# jack2jst.net
KiCad netlist of a schematic drawn in EAGLE
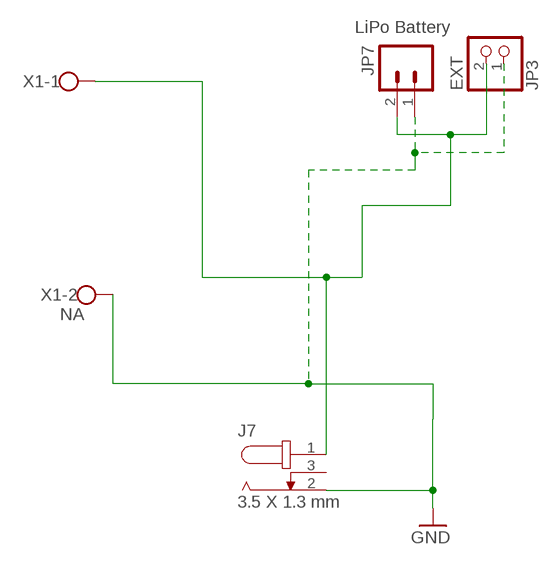
[diagram p0: schematic, sheet 1]

(export (version "E")
  (design (tool "Eeschema 10.0.6"))
  (components
    (comp (ref "J7")
      (value "3.5 X 1.3 mm")
      (footprint "eagle-import:3.5X1.3MM_DC_JACK")
      (libsource (lib "eagle-import") (part "DC_JACK_3.5X1.3MM"))
    )
    (comp (ref "JP3")
      (value "EXT")
      (footprint "eagle-import:1X02")
      (libsource (lib "eagle-import") (part "PINHD-1X2"))
    )
    (comp (ref "JP7")
      (value "LiPo Battery")
      (footprint "eagle-import:JST-2-PTH")
      (libsource (lib "eagle-import") (part "M02JST-PTH-2"))
    )
    (comp (ref "X1")
      (value "NA")
      (footprint "eagle-import:W237-102")
      (libsource (lib "eagle-import") (part "W237-102"))
    )
  )
  (nets
    (net (code "1") (name "GND") (class "Default")
      (node (ref "J7") (pin "2") (pinfunction "2_2") (pintype "passive"))
      (node (ref "JP3") (pin "1") (pinfunction "1_1") (pintype "passive"))
      (node (ref "JP7") (pin "1") (pinfunction "1_1") (pintype "passive"))
      (node (ref "X1") (pin "2") (pinfunction "KL_2") (pintype "passive"))
    )
    (net (code "2") (name "Net-(X1A-KL)") (class "Default")
      (node (ref "J7") (pin "1") (pinfunction "1_1") (pintype "passive"))
      (node (ref "JP3") (pin "2") (pinfunction "2_2") (pintype "passive"))
      (node (ref "JP7") (pin "2") (pinfunction "2_2") (pintype "passive"))
      (node (ref "X1") (pin "1") (pinfunction "KL_1") (pintype "passive"))
    )
    (net (code "3") (name "unconnected-(J7-Pad3)") (class "Default")
      (node (ref "J7") (pin "3") (pinfunction "3_3") (pintype "passive"))
    )
  )
)
